# TeensyViewTopTest.net
KiCad netlist of a schematic drawn in EAGLE
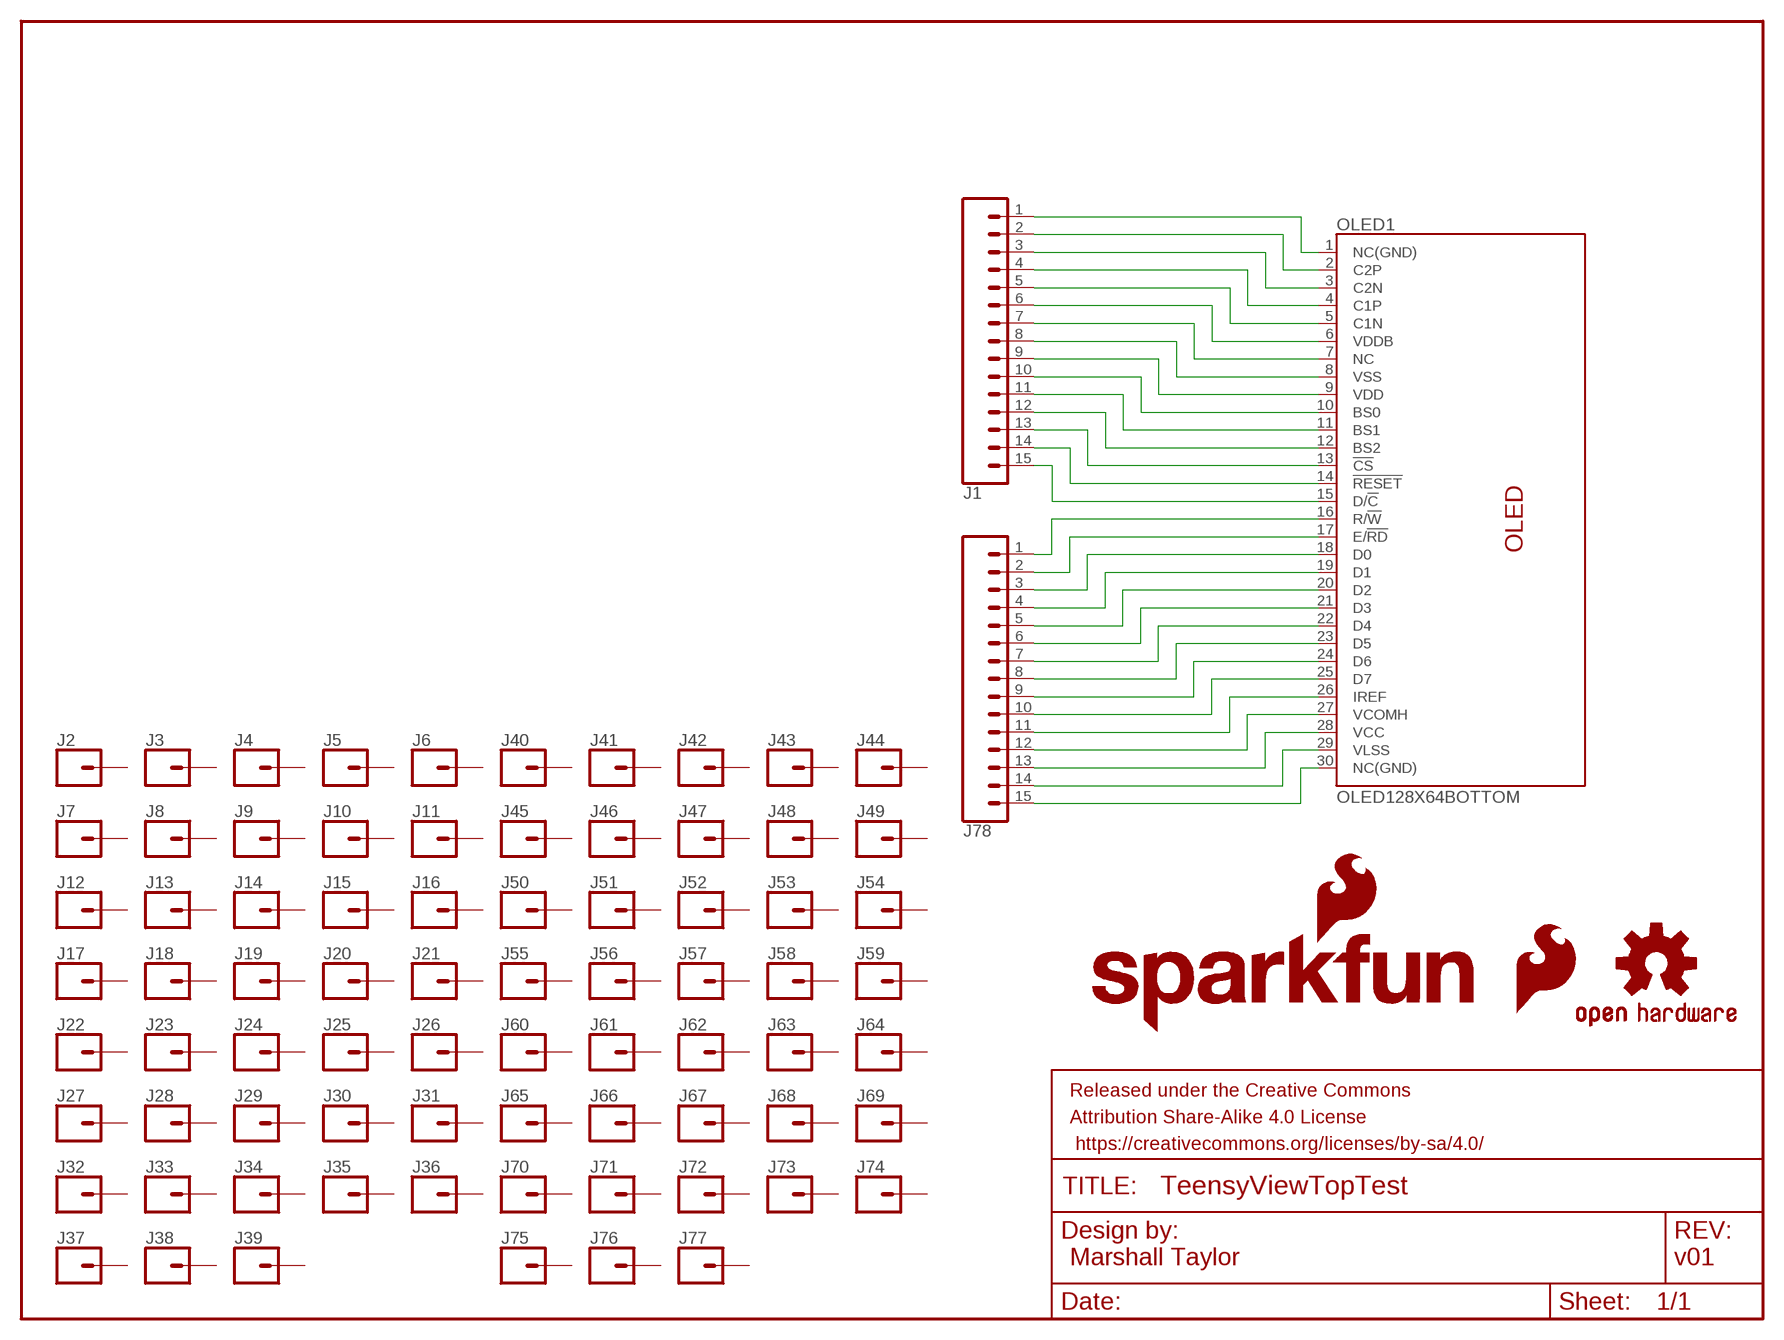
[diagram p0: schematic, sheet 1]

(export (version "E")
  (design (tool "Eeschema 10.0.6"))
  (components
    (comp (ref "FRAME1")
      (value "FRAME-LETTER")
      (footprint "eagle-import:CREATIVE_COMMONS")
      (libsource (lib "eagle-import") (part "FRAME-LETTER"))
    )
    (comp (ref "J1")
      (value "CONN_15")
      (footprint "eagle-import:1X15")
      (libsource (lib "eagle-import") (part "CONN_15"))
    )
    (comp (ref "J2")
      (value "CONN_01PTH_NO_SILK_YES_STOP")
      (footprint "eagle-import:1X01_NO_SILK")
      (libsource (lib "eagle-import") (part "CONN_01PTH_NO_SILK_YES_STOP"))
    )
    (comp (ref "J3")
      (value "CONN_01PTH_NO_SILK_YES_STOP")
      (footprint "eagle-import:1X01_NO_SILK")
      (libsource (lib "eagle-import") (part "CONN_01PTH_NO_SILK_YES_STOP"))
    )
    (comp (ref "J4")
      (value "CONN_01PTH_NO_SILK_YES_STOP")
      (footprint "eagle-import:1X01_NO_SILK")
      (libsource (lib "eagle-import") (part "CONN_01PTH_NO_SILK_YES_STOP"))
    )
    (comp (ref "J5")
      (value "CONN_01PTH_NO_SILK_YES_STOP")
      (footprint "eagle-import:1X01_NO_SILK")
      (libsource (lib "eagle-import") (part "CONN_01PTH_NO_SILK_YES_STOP"))
    )
    (comp (ref "J6")
      (value "CONN_01PTH_NO_SILK_YES_STOP")
      (footprint "eagle-import:1X01_NO_SILK")
      (libsource (lib "eagle-import") (part "CONN_01PTH_NO_SILK_YES_STOP"))
    )
    (comp (ref "J7")
      (value "CONN_01PTH_NO_SILK_YES_STOP")
      (footprint "eagle-import:1X01_NO_SILK")
      (libsource (lib "eagle-import") (part "CONN_01PTH_NO_SILK_YES_STOP"))
    )
    (comp (ref "J8")
      (value "CONN_01PTH_NO_SILK_YES_STOP")
      (footprint "eagle-import:1X01_NO_SILK")
      (libsource (lib "eagle-import") (part "CONN_01PTH_NO_SILK_YES_STOP"))
    )
    (comp (ref "J9")
      (value "CONN_01PTH_NO_SILK_YES_STOP")
      (footprint "eagle-import:1X01_NO_SILK")
      (libsource (lib "eagle-import") (part "CONN_01PTH_NO_SILK_YES_STOP"))
    )
    (comp (ref "J10")
      (value "CONN_01PTH_NO_SILK_YES_STOP")
      (footprint "eagle-import:1X01_NO_SILK")
      (libsource (lib "eagle-import") (part "CONN_01PTH_NO_SILK_YES_STOP"))
    )
    (comp (ref "J11")
      (value "CONN_01PTH_NO_SILK_YES_STOP")
      (footprint "eagle-import:1X01_NO_SILK")
      (libsource (lib "eagle-import") (part "CONN_01PTH_NO_SILK_YES_STOP"))
    )
    (comp (ref "J12")
      (value "CONN_01PTH_NO_SILK_YES_STOP")
      (footprint "eagle-import:1X01_NO_SILK")
      (libsource (lib "eagle-import") (part "CONN_01PTH_NO_SILK_YES_STOP"))
    )
    (comp (ref "J13")
      (value "CONN_01PTH_NO_SILK_YES_STOP")
      (footprint "eagle-import:1X01_NO_SILK")
      (libsource (lib "eagle-import") (part "CONN_01PTH_NO_SILK_YES_STOP"))
    )
    (comp (ref "J14")
      (value "CONN_01PTH_NO_SILK_YES_STOP")
      (footprint "eagle-import:1X01_NO_SILK")
      (libsource (lib "eagle-import") (part "CONN_01PTH_NO_SILK_YES_STOP"))
    )
    (comp (ref "J15")
      (value "CONN_01PTH_NO_SILK_YES_STOP")
      (footprint "eagle-import:1X01_NO_SILK")
      (libsource (lib "eagle-import") (part "CONN_01PTH_NO_SILK_YES_STOP"))
    )
    (comp (ref "J16")
      (value "CONN_01PTH_NO_SILK_YES_STOP")
      (footprint "eagle-import:1X01_NO_SILK")
      (libsource (lib "eagle-import") (part "CONN_01PTH_NO_SILK_YES_STOP"))
    )
    (comp (ref "J17")
      (value "CONN_01PTH_NO_SILK_YES_STOP")
      (footprint "eagle-import:1X01_NO_SILK")
      (libsource (lib "eagle-import") (part "CONN_01PTH_NO_SILK_YES_STOP"))
    )
    (comp (ref "J18")
      (value "CONN_01PTH_NO_SILK_YES_STOP")
      (footprint "eagle-import:1X01_NO_SILK")
      (libsource (lib "eagle-import") (part "CONN_01PTH_NO_SILK_YES_STOP"))
    )
    (comp (ref "J19")
      (value "CONN_01PTH_NO_SILK_YES_STOP")
      (footprint "eagle-import:1X01_NO_SILK")
      (libsource (lib "eagle-import") (part "CONN_01PTH_NO_SILK_YES_STOP"))
    )
    (comp (ref "J20")
      (value "CONN_01PTH_NO_SILK_YES_STOP")
      (footprint "eagle-import:1X01_NO_SILK")
      (libsource (lib "eagle-import") (part "CONN_01PTH_NO_SILK_YES_STOP"))
    )
    (comp (ref "J21")
      (value "CONN_01PTH_NO_SILK_YES_STOP")
      (footprint "eagle-import:1X01_NO_SILK")
      (libsource (lib "eagle-import") (part "CONN_01PTH_NO_SILK_YES_STOP"))
    )
    (comp (ref "J22")
      (value "CONN_01PTH_NO_SILK_YES_STOP")
      (footprint "eagle-import:1X01_NO_SILK")
      (libsource (lib "eagle-import") (part "CONN_01PTH_NO_SILK_YES_STOP"))
    )
    (comp (ref "J23")
      (value "CONN_01PTH_NO_SILK_YES_STOP")
      (footprint "eagle-import:1X01_NO_SILK")
      (libsource (lib "eagle-import") (part "CONN_01PTH_NO_SILK_YES_STOP"))
    )
    (comp (ref "J24")
      (value "CONN_01PTH_NO_SILK_YES_STOP")
      (footprint "eagle-import:1X01_NO_SILK")
      (libsource (lib "eagle-import") (part "CONN_01PTH_NO_SILK_YES_STOP"))
    )
    (comp (ref "J25")
      (value "CONN_01PTH_NO_SILK_YES_STOP")
      (footprint "eagle-import:1X01_NO_SILK")
      (libsource (lib "eagle-import") (part "CONN_01PTH_NO_SILK_YES_STOP"))
    )
    (comp (ref "J26")
      (value "CONN_01PTH_NO_SILK_YES_STOP")
      (footprint "eagle-import:1X01_NO_SILK")
      (libsource (lib "eagle-import") (part "CONN_01PTH_NO_SILK_YES_STOP"))
    )
    (comp (ref "J27")
      (value "CONN_01PTH_NO_SILK_YES_STOP")
      (footprint "eagle-import:1X01_NO_SILK")
      (libsource (lib "eagle-import") (part "CONN_01PTH_NO_SILK_YES_STOP"))
    )
    (comp (ref "J28")
      (value "CONN_01PTH_NO_SILK_YES_STOP")
      (footprint "eagle-import:1X01_NO_SILK")
      (libsource (lib "eagle-import") (part "CONN_01PTH_NO_SILK_YES_STOP"))
    )
    (comp (ref "J29")
      (value "CONN_01PTH_NO_SILK_YES_STOP")
      (footprint "eagle-import:1X01_NO_SILK")
      (libsource (lib "eagle-import") (part "CONN_01PTH_NO_SILK_YES_STOP"))
    )
    (comp (ref "J30")
      (value "CONN_01PTH_NO_SILK_YES_STOP")
      (footprint "eagle-import:1X01_NO_SILK")
      (libsource (lib "eagle-import") (part "CONN_01PTH_NO_SILK_YES_STOP"))
    )
    (comp (ref "J31")
      (value "CONN_01PTH_NO_SILK_YES_STOP")
      (footprint "eagle-import:1X01_NO_SILK")
      (libsource (lib "eagle-import") (part "CONN_01PTH_NO_SILK_YES_STOP"))
    )
    (comp (ref "J32")
      (value "CONN_01PTH_NO_SILK_YES_STOP")
      (footprint "eagle-import:1X01_NO_SILK")
      (libsource (lib "eagle-import") (part "CONN_01PTH_NO_SILK_YES_STOP"))
    )
    (comp (ref "J33")
      (value "CONN_01PTH_NO_SILK_YES_STOP")
      (footprint "eagle-import:1X01_NO_SILK")
      (libsource (lib "eagle-import") (part "CONN_01PTH_NO_SILK_YES_STOP"))
    )
    (comp (ref "J34")
      (value "CONN_01PTH_NO_SILK_YES_STOP")
      (footprint "eagle-import:1X01_NO_SILK")
      (libsource (lib "eagle-import") (part "CONN_01PTH_NO_SILK_YES_STOP"))
    )
    (comp (ref "J35")
      (value "CONN_01PTH_NO_SILK_YES_STOP")
      (footprint "eagle-import:1X01_NO_SILK")
      (libsource (lib "eagle-import") (part "CONN_01PTH_NO_SILK_YES_STOP"))
    )
    (comp (ref "J36")
      (value "CONN_01PTH_NO_SILK_YES_STOP")
      (footprint "eagle-import:1X01_NO_SILK")
      (libsource (lib "eagle-import") (part "CONN_01PTH_NO_SILK_YES_STOP"))
    )
    (comp (ref "J37")
      (value "CONN_01PTH_NO_SILK_YES_STOP")
      (footprint "eagle-import:1X01_NO_SILK")
      (libsource (lib "eagle-import") (part "CONN_01PTH_NO_SILK_YES_STOP"))
    )
    (comp (ref "J38")
      (value "CONN_01PTH_NO_SILK_YES_STOP")
      (footprint "eagle-import:1X01_NO_SILK")
      (libsource (lib "eagle-import") (part "CONN_01PTH_NO_SILK_YES_STOP"))
    )
    (comp (ref "J39")
      (value "CONN_01PTH_NO_SILK_YES_STOP")
      (footprint "eagle-import:1X01_NO_SILK")
      (libsource (lib "eagle-import") (part "CONN_01PTH_NO_SILK_YES_STOP"))
    )
    (comp (ref "J40")
      (value "CONN_01PTH_NO_SILK_YES_STOP")
      (footprint "eagle-import:1X01_NO_SILK")
      (libsource (lib "eagle-import") (part "CONN_01PTH_NO_SILK_YES_STOP"))
    )
    (comp (ref "J41")
      (value "CONN_01PTH_NO_SILK_YES_STOP")
      (footprint "eagle-import:1X01_NO_SILK")
      (libsource (lib "eagle-import") (part "CONN_01PTH_NO_SILK_YES_STOP"))
    )
    (comp (ref "J42")
      (value "CONN_01PTH_NO_SILK_YES_STOP")
      (footprint "eagle-import:1X01_NO_SILK")
      (libsource (lib "eagle-import") (part "CONN_01PTH_NO_SILK_YES_STOP"))
    )
    (comp (ref "J43")
      (value "CONN_01PTH_NO_SILK_YES_STOP")
      (footprint "eagle-import:1X01_NO_SILK")
      (libsource (lib "eagle-import") (part "CONN_01PTH_NO_SILK_YES_STOP"))
    )
    (comp (ref "J44")
      (value "CONN_01PTH_NO_SILK_YES_STOP")
      (footprint "eagle-import:1X01_NO_SILK")
      (libsource (lib "eagle-import") (part "CONN_01PTH_NO_SILK_YES_STOP"))
    )
    (comp (ref "J45")
      (value "CONN_01PTH_NO_SILK_YES_STOP")
      (footprint "eagle-import:1X01_NO_SILK")
      (libsource (lib "eagle-import") (part "CONN_01PTH_NO_SILK_YES_STOP"))
    )
    (comp (ref "J46")
      (value "CONN_01PTH_NO_SILK_YES_STOP")
      (footprint "eagle-import:1X01_NO_SILK")
      (libsource (lib "eagle-import") (part "CONN_01PTH_NO_SILK_YES_STOP"))
    )
    (comp (ref "J47")
      (value "CONN_01PTH_NO_SILK_YES_STOP")
      (footprint "eagle-import:1X01_NO_SILK")
      (libsource (lib "eagle-import") (part "CONN_01PTH_NO_SILK_YES_STOP"))
    )
    (comp (ref "J48")
      (value "CONN_01PTH_NO_SILK_YES_STOP")
      (footprint "eagle-import:1X01_NO_SILK")
      (libsource (lib "eagle-import") (part "CONN_01PTH_NO_SILK_YES_STOP"))
    )
    (comp (ref "J49")
      (value "CONN_01PTH_NO_SILK_YES_STOP")
      (footprint "eagle-import:1X01_NO_SILK")
      (libsource (lib "eagle-import") (part "CONN_01PTH_NO_SILK_YES_STOP"))
    )
    (comp (ref "J50")
      (value "CONN_01PTH_NO_SILK_YES_STOP")
      (footprint "eagle-import:1X01_NO_SILK")
      (libsource (lib "eagle-import") (part "CONN_01PTH_NO_SILK_YES_STOP"))
    )
    (comp (ref "J51")
      (value "CONN_01PTH_NO_SILK_YES_STOP")
      (footprint "eagle-import:1X01_NO_SILK")
      (libsource (lib "eagle-import") (part "CONN_01PTH_NO_SILK_YES_STOP"))
    )
    (comp (ref "J52")
      (value "CONN_01PTH_NO_SILK_YES_STOP")
      (footprint "eagle-import:1X01_NO_SILK")
      (libsource (lib "eagle-import") (part "CONN_01PTH_NO_SILK_YES_STOP"))
    )
    (comp (ref "J53")
      (value "CONN_01PTH_NO_SILK_YES_STOP")
      (footprint "eagle-import:1X01_NO_SILK")
      (libsource (lib "eagle-import") (part "CONN_01PTH_NO_SILK_YES_STOP"))
    )
    (comp (ref "J54")
      (value "CONN_01PTH_NO_SILK_YES_STOP")
      (footprint "eagle-import:1X01_NO_SILK")
      (libsource (lib "eagle-import") (part "CONN_01PTH_NO_SILK_YES_STOP"))
    )
    (comp (ref "J55")
      (value "CONN_01PTH_NO_SILK_YES_STOP")
      (footprint "eagle-import:1X01_NO_SILK")
      (libsource (lib "eagle-import") (part "CONN_01PTH_NO_SILK_YES_STOP"))
    )
    (comp (ref "J56")
      (value "CONN_01PTH_NO_SILK_YES_STOP")
      (footprint "eagle-import:1X01_NO_SILK")
      (libsource (lib "eagle-import") (part "CONN_01PTH_NO_SILK_YES_STOP"))
    )
    (comp (ref "J57")
      (value "CONN_01PTH_NO_SILK_YES_STOP")
      (footprint "eagle-import:1X01_NO_SILK")
      (libsource (lib "eagle-import") (part "CONN_01PTH_NO_SILK_YES_STOP"))
    )
    (comp (ref "J58")
      (value "CONN_01PTH_NO_SILK_YES_STOP")
      (footprint "eagle-import:1X01_NO_SILK")
      (libsource (lib "eagle-import") (part "CONN_01PTH_NO_SILK_YES_STOP"))
    )
    (comp (ref "J59")
      (value "CONN_01PTH_NO_SILK_YES_STOP")
      (footprint "eagle-import:1X01_NO_SILK")
      (libsource (lib "eagle-import") (part "CONN_01PTH_NO_SILK_YES_STOP"))
    )
    (comp (ref "J60")
      (value "CONN_01PTH_NO_SILK_YES_STOP")
      (footprint "eagle-import:1X01_NO_SILK")
      (libsource (lib "eagle-import") (part "CONN_01PTH_NO_SILK_YES_STOP"))
    )
    (comp (ref "J61")
      (value "CONN_01PTH_NO_SILK_YES_STOP")
      (footprint "eagle-import:1X01_NO_SILK")
      (libsource (lib "eagle-import") (part "CONN_01PTH_NO_SILK_YES_STOP"))
    )
    (comp (ref "J62")
      (value "CONN_01PTH_NO_SILK_YES_STOP")
      (footprint "eagle-import:1X01_NO_SILK")
      (libsource (lib "eagle-import") (part "CONN_01PTH_NO_SILK_YES_STOP"))
    )
    (comp (ref "J63")
      (value "CONN_01PTH_NO_SILK_YES_STOP")
      (footprint "eagle-import:1X01_NO_SILK")
      (libsource (lib "eagle-import") (part "CONN_01PTH_NO_SILK_YES_STOP"))
    )
    (comp (ref "J64")
      (value "CONN_01PTH_NO_SILK_YES_STOP")
      (footprint "eagle-import:1X01_NO_SILK")
      (libsource (lib "eagle-import") (part "CONN_01PTH_NO_SILK_YES_STOP"))
    )
    (comp (ref "J65")
      (value "CONN_01PTH_NO_SILK_YES_STOP")
      (footprint "eagle-import:1X01_NO_SILK")
      (libsource (lib "eagle-import") (part "CONN_01PTH_NO_SILK_YES_STOP"))
    )
    (comp (ref "J66")
      (value "CONN_01PTH_NO_SILK_YES_STOP")
      (footprint "eagle-import:1X01_NO_SILK")
      (libsource (lib "eagle-import") (part "CONN_01PTH_NO_SILK_YES_STOP"))
    )
    (comp (ref "J67")
      (value "CONN_01PTH_NO_SILK_YES_STOP")
      (footprint "eagle-import:1X01_NO_SILK")
      (libsource (lib "eagle-import") (part "CONN_01PTH_NO_SILK_YES_STOP"))
    )
    (comp (ref "J68")
      (value "CONN_01PTH_NO_SILK_YES_STOP")
      (footprint "eagle-import:1X01_NO_SILK")
      (libsource (lib "eagle-import") (part "CONN_01PTH_NO_SILK_YES_STOP"))
    )
    (comp (ref "J69")
      (value "CONN_01PTH_NO_SILK_YES_STOP")
      (footprint "eagle-import:1X01_NO_SILK")
      (libsource (lib "eagle-import") (part "CONN_01PTH_NO_SILK_YES_STOP"))
    )
    (comp (ref "J70")
      (value "CONN_01PTH_NO_SILK_YES_STOP")
      (footprint "eagle-import:1X01_NO_SILK")
      (libsource (lib "eagle-import") (part "CONN_01PTH_NO_SILK_YES_STOP"))
    )
    (comp (ref "J71")
      (value "CONN_01PTH_NO_SILK_YES_STOP")
      (footprint "eagle-import:1X01_NO_SILK")
      (libsource (lib "eagle-import") (part "CONN_01PTH_NO_SILK_YES_STOP"))
    )
    (comp (ref "J72")
      (value "CONN_01PTH_NO_SILK_YES_STOP")
      (footprint "eagle-import:1X01_NO_SILK")
      (libsource (lib "eagle-import") (part "CONN_01PTH_NO_SILK_YES_STOP"))
    )
    (comp (ref "J73")
      (value "CONN_01PTH_NO_SILK_YES_STOP")
      (footprint "eagle-import:1X01_NO_SILK")
      (libsource (lib "eagle-import") (part "CONN_01PTH_NO_SILK_YES_STOP"))
    )
    (comp (ref "J74")
      (value "CONN_01PTH_NO_SILK_YES_STOP")
      (footprint "eagle-import:1X01_NO_SILK")
      (libsource (lib "eagle-import") (part "CONN_01PTH_NO_SILK_YES_STOP"))
    )
    (comp (ref "J75")
      (value "CONN_01PTH_NO_SILK_YES_STOP")
      (footprint "eagle-import:1X01_NO_SILK")
      (libsource (lib "eagle-import") (part "CONN_01PTH_NO_SILK_YES_STOP"))
    )
    (comp (ref "J76")
      (value "CONN_01PTH_NO_SILK_YES_STOP")
      (footprint "eagle-import:1X01_NO_SILK")
      (libsource (lib "eagle-import") (part "CONN_01PTH_NO_SILK_YES_STOP"))
    )
    (comp (ref "J77")
      (value "CONN_01PTH_NO_SILK_YES_STOP")
      (footprint "eagle-import:1X01_NO_SILK")
      (libsource (lib "eagle-import") (part "CONN_01PTH_NO_SILK_YES_STOP"))
    )
    (comp (ref "J78")
      (value "CONN_15")
      (footprint "eagle-import:1X15")
      (libsource (lib "eagle-import") (part "CONN_15"))
    )
    (comp (ref "LOGO1")
      (value "SFE_LOGO_FLAME.1_INCH")
      (footprint "eagle-import:SFE_LOGO_FLAME_.1")
      (libsource (lib "eagle-import") (part "SFE_LOGO_FLAME.1_INCH"))
    )
    (comp (ref "LOGO2")
      (value "OSHW-LOGOS")
      (footprint "eagle-import:OSHW-LOGO-S")
      (libsource (lib "eagle-import") (part "OSHW-LOGOS"))
    )
    (comp (ref "LOGO3")
      (value "SFE_LOGO_NAME_FLAME.1_INCH")
      (footprint "eagle-import:SFE_LOGO_NAME_FLAME_.1")
      (libsource (lib "eagle-import") (part "SFE_LOGO_NAME_FLAME.1_INCH"))
    )
    (comp (ref "OLED1")
      (value "OLED128X64BOTTOM")
      (footprint "eagle-import:OLED-UG-2832HLBEG04")
      (libsource (lib "eagle-import") (part "OLED128X64BOTTOM"))
    )
  )
  (nets
    (net (code "1") (name "Net-(J1-Pad1)") (class "Default")
      (node (ref "J1") (pin "1") (pinfunction "1_1") (pintype "passive"))
      (node (ref "OLED1") (pin "1") (pinfunction "NC(GND)_1") (pintype "bidirectional"))
    )
    (net (code "2") (name "Net-(J78-Pad15)") (class "Default")
      (node (ref "J78") (pin "15") (pinfunction "15_15") (pintype "passive"))
      (node (ref "OLED1") (pin "30") (pinfunction "NC(GND)_30") (pintype "bidirectional"))
    )
    (net (code "3") (name "Net-(OLED1-BS0)") (class "Default")
      (node (ref "J1") (pin "10") (pinfunction "10_10") (pintype "passive"))
      (node (ref "OLED1") (pin "10") (pinfunction "BS0_10") (pintype "bidirectional"))
    )
    (net (code "4") (name "Net-(OLED1-BS1)") (class "Default")
      (node (ref "J1") (pin "11") (pinfunction "11_11") (pintype "passive"))
      (node (ref "OLED1") (pin "11") (pinfunction "BS1_11") (pintype "bidirectional"))
    )
    (net (code "5") (name "Net-(OLED1-BS2)") (class "Default")
      (node (ref "J1") (pin "12") (pinfunction "12_12") (pintype "passive"))
      (node (ref "OLED1") (pin "12") (pinfunction "BS2_12") (pintype "bidirectional"))
    )
    (net (code "6") (name "Net-(OLED1-C1N)") (class "Default")
      (node (ref "J1") (pin "5") (pinfunction "5_5") (pintype "passive"))
      (node (ref "OLED1") (pin "5") (pinfunction "C1N_5") (pintype "bidirectional"))
    )
    (net (code "7") (name "Net-(OLED1-C1P)") (class "Default")
      (node (ref "J1") (pin "4") (pinfunction "4_4") (pintype "passive"))
      (node (ref "OLED1") (pin "4") (pinfunction "C1P_4") (pintype "bidirectional"))
    )
    (net (code "8") (name "Net-(OLED1-C2N)") (class "Default")
      (node (ref "J1") (pin "3") (pinfunction "3_3") (pintype "passive"))
      (node (ref "OLED1") (pin "3") (pinfunction "C2N_3") (pintype "bidirectional"))
    )
    (net (code "9") (name "Net-(OLED1-C2P)") (class "Default")
      (node (ref "J1") (pin "2") (pinfunction "2_2") (pintype "passive"))
      (node (ref "OLED1") (pin "2") (pinfunction "C2P_2") (pintype "bidirectional"))
    )
    (net (code "10") (name "Net-(OLED1-D0)") (class "Default")
      (node (ref "J78") (pin "3") (pinfunction "3_3") (pintype "passive"))
      (node (ref "OLED1") (pin "18") (pinfunction "D0_18") (pintype "bidirectional"))
    )
    (net (code "11") (name "Net-(OLED1-D1)") (class "Default")
      (node (ref "J78") (pin "4") (pinfunction "4_4") (pintype "passive"))
      (node (ref "OLED1") (pin "19") (pinfunction "D1_19") (pintype "bidirectional"))
    )
    (net (code "12") (name "Net-(OLED1-D2)") (class "Default")
      (node (ref "J78") (pin "5") (pinfunction "5_5") (pintype "passive"))
      (node (ref "OLED1") (pin "20") (pinfunction "D2_20") (pintype "bidirectional"))
    )
    (net (code "13") (name "Net-(OLED1-D3)") (class "Default")
      (node (ref "J78") (pin "6") (pinfunction "6_6") (pintype "passive"))
      (node (ref "OLED1") (pin "21") (pinfunction "D3_21") (pintype "bidirectional"))
    )
    (net (code "14") (name "Net-(OLED1-D4)") (class "Default")
      (node (ref "J78") (pin "7") (pinfunction "7_7") (pintype "passive"))
      (node (ref "OLED1") (pin "22") (pinfunction "D4_22") (pintype "bidirectional"))
    )
    (net (code "15") (name "Net-(OLED1-D5)") (class "Default")
      (node (ref "J78") (pin "8") (pinfunction "8_8") (pintype "passive"))
      (node (ref "OLED1") (pin "23") (pinfunction "D5_23") (pintype "bidirectional"))
    )
    (net (code "16") (name "Net-(OLED1-D6)") (class "Default")
      (node (ref "J78") (pin "9") (pinfunction "9_9") (pintype "passive"))
      (node (ref "OLED1") (pin "24") (pinfunction "D6_24") (pintype "bidirectional"))
    )
    (net (code "17") (name "Net-(OLED1-D7)") (class "Default")
      (node (ref "J78") (pin "10") (pinfunction "10_10") (pintype "passive"))
      (node (ref "OLED1") (pin "25") (pinfunction "D7_25") (pintype "bidirectional"))
    )
    (net (code "18") (name "Net-(OLED1-D{slash}~{C})") (class "Default")
      (node (ref "J1") (pin "15") (pinfunction "15_15") (pintype "passive"))
      (node (ref "OLED1") (pin "15") (pinfunction "D/~{C}_15") (pintype "bidirectional"))
    )
    (net (code "19") (name "Net-(OLED1-E{slash}~{RD})") (class "Default")
      (node (ref "J78") (pin "2") (pinfunction "2_2") (pintype "passive"))
      (node (ref "OLED1") (pin "17") (pinfunction "E/~{RD}_17") (pintype "bidirectional"))
    )
    (net (code "20") (name "Net-(OLED1-IREF)") (class "Default")
      (node (ref "J78") (pin "11") (pinfunction "11_11") (pintype "passive"))
      (node (ref "OLED1") (pin "26") (pinfunction "IREF_26") (pintype "bidirectional"))
    )
    (net (code "21") (name "Net-(OLED1-NC)") (class "Default")
      (node (ref "J1") (pin "7") (pinfunction "7_7") (pintype "passive"))
      (node (ref "OLED1") (pin "7") (pinfunction "NC_7") (pintype "bidirectional"))
    )
    (net (code "22") (name "Net-(OLED1-R{slash}~{W})") (class "Default")
      (node (ref "J78") (pin "1") (pinfunction "1_1") (pintype "passive"))
      (node (ref "OLED1") (pin "16") (pinfunction "R/~{W}_16") (pintype "bidirectional"))
    )
    (net (code "23") (name "Net-(OLED1-VCC)") (class "Default")
      (node (ref "J78") (pin "13") (pinfunction "13_13") (pintype "passive"))
      (node (ref "OLED1") (pin "28") (pinfunction "VCC_28") (pintype "bidirectional"))
    )
    (net (code "24") (name "Net-(OLED1-VCOMH)") (class "Default")
      (node (ref "J78") (pin "12") (pinfunction "12_12") (pintype "passive"))
      (node (ref "OLED1") (pin "27") (pinfunction "VCOMH_27") (pintype "bidirectional"))
    )
    (net (code "25") (name "Net-(OLED1-VDD)") (class "Default")
      (node (ref "J1") (pin "9") (pinfunction "9_9") (pintype "passive"))
      (node (ref "OLED1") (pin "9") (pinfunction "VDD_9") (pintype "bidirectional"))
    )
    (net (code "26") (name "Net-(OLED1-VDDB)") (class "Default")
      (node (ref "J1") (pin "6") (pinfunction "6_6") (pintype "passive"))
      (node (ref "OLED1") (pin "6") (pinfunction "VDDB_6") (pintype "bidirectional"))
    )
    (net (code "27") (name "Net-(OLED1-VLSS)") (class "Default")
      (node (ref "J78") (pin "14") (pinfunction "14_14") (pintype "passive"))
      (node (ref "OLED1") (pin "29") (pinfunction "VLSS_29") (pintype "bidirectional"))
    )
    (net (code "28") (name "Net-(OLED1-VSS)") (class "Default")
      (node (ref "J1") (pin "8") (pinfunction "8_8") (pintype "passive"))
      (node (ref "OLED1") (pin "8") (pinfunction "VSS_8") (pintype "bidirectional"))
    )
    (net (code "29") (name "Net-(OLED1-~{CS})") (class "Default")
      (node (ref "J1") (pin "13") (pinfunction "13_13") (pintype "passive"))
      (node (ref "OLED1") (pin "13") (pinfunction "~{CS}_13") (pintype "bidirectional"))
    )
    (net (code "30") (name "Net-(OLED1-~{RESET})") (class "Default")
      (node (ref "J1") (pin "14") (pinfunction "14_14") (pintype "passive"))
      (node (ref "OLED1") (pin "14") (pinfunction "~{RESET}_14") (pintype "bidirectional"))
    )
    (net (code "31") (name "unconnected-(J2-Pad1)") (class "Default")
      (node (ref "J2") (pin "1") (pinfunction "1_1") (pintype "passive"))
    )
    (net (code "32") (name "unconnected-(J3-Pad1)") (class "Default")
      (node (ref "J3") (pin "1") (pinfunction "1_1") (pintype "passive"))
    )
    (net (code "33") (name "unconnected-(J4-Pad1)") (class "Default")
      (node (ref "J4") (pin "1") (pinfunction "1_1") (pintype "passive"))
    )
    (net (code "34") (name "unconnected-(J5-Pad1)") (class "Default")
      (node (ref "J5") (pin "1") (pinfunction "1_1") (pintype "passive"))
    )
    (net (code "35") (name "unconnected-(J6-Pad1)") (class "Default")
      (node (ref "J6") (pin "1") (pinfunction "1_1") (pintype "passive"))
    )
    (net (code "36") (name "unconnected-(J7-Pad1)") (class "Default")
      (node (ref "J7") (pin "1") (pinfunction "1_1") (pintype "passive"))
    )
    (net (code "37") (name "unconnected-(J8-Pad1)") (class "Default")
      (node (ref "J8") (pin "1") (pinfunction "1_1") (pintype "passive"))
    )
    (net (code "38") (name "unconnected-(J9-Pad1)") (class "Default")
      (node (ref "J9") (pin "1") (pinfunction "1_1") (pintype "passive"))
    )
    (net (code "39") (name "unconnected-(J10-Pad1)") (class "Default")
      (node (ref "J10") (pin "1") (pinfunction "1_1") (pintype "passive"))
    )
    (net (code "40") (name "unconnected-(J11-Pad1)") (class "Default")
      (node (ref "J11") (pin "1") (pinfunction "1_1") (pintype "passive"))
    )
    (net (code "41") (name "unconnected-(J12-Pad1)") (class "Default")
      (node (ref "J12") (pin "1") (pinfunction "1_1") (pintype "passive"))
    )
    (net (code "42") (name "unconnected-(J13-Pad1)") (class "Default")
      (node (ref "J13") (pin "1") (pinfunction "1_1") (pintype "passive"))
    )
    (net (code "43") (name "unconnected-(J14-Pad1)") (class "Default")
      (node (ref "J14") (pin "1") (pinfunction "1_1") (pintype "passive"))
    )
    (net (code "44") (name "unconnected-(J15-Pad1)") (class "Default")
      (node (ref "J15") (pin "1") (pinfunction "1_1") (pintype "passive"))
    )
    (net (code "45") (name "unconnected-(J16-Pad1)") (class "Default")
      (node (ref "J16") (pin "1") (pinfunction "1_1") (pintype "passive"))
    )
    (net (code "46") (name "unconnected-(J17-Pad1)") (class "Default")
      (node (ref "J17") (pin "1") (pinfunction "1_1") (pintype "passive"))
    )
    (net (code "47") (name "unconnected-(J18-Pad1)") (class "Default")
      (node (ref "J18") (pin "1") (pinfunction "1_1") (pintype "passive"))
    )
    (net (code "48") (name "unconnected-(J19-Pad1)") (class "Default")
      (node (ref "J19") (pin "1") (pinfunction "1_1") (pintype "passive"))
    )
    (net (code "49") (name "unconnected-(J20-Pad1)") (class "Default")
      (node (ref "J20") (pin "1") (pinfunction "1_1") (pintype "passive"))
    )
    (net (code "50") (name "unconnected-(J21-Pad1)") (class "Default")
      (node (ref "J21") (pin "1") (pinfunction "1_1") (pintype "passive"))
    )
    (net (code "51") (name "unconnected-(J22-Pad1)") (class "Default")
      (node (ref "J22") (pin "1") (pinfunction "1_1") (pintype "passive"))
    )
    (net (code "52") (name "unconnected-(J23-Pad1)") (class "Default")
      (node (ref "J23") (pin "1") (pinfunction "1_1") (pintype "passive"))
    )
    (net (code "53") (name "unconnected-(J24-Pad1)") (class "Default")
      (node (ref "J24") (pin "1") (pinfunction "1_1") (pintype "passive"))
    )
    (net (code "54") (name "unconnected-(J25-Pad1)") (class "Default")
      (node (ref "J25") (pin "1") (pinfunction "1_1") (pintype "passive"))
    )
    (net (code "55") (name "unconnected-(J26-Pad1)") (class "Default")
      (node (ref "J26") (pin "1") (pinfunction "1_1") (pintype "passive"))
    )
    (net (code "56") (name "unconnected-(J27-Pad1)") (class "Default")
      (node (ref "J27") (pin "1") (pinfunction "1_1") (pintype "passive"))
    )
    (net (code "57") (name "unconnected-(J28-Pad1)") (class "Default")
      (node (ref "J28") (pin "1") (pinfunction "1_1") (pintype "passive"))
    )
    (net (code "58") (name "unconnected-(J29-Pad1)") (class "Default")
      (node (ref "J29") (pin "1") (pinfunction "1_1") (pintype "passive"))
    )
    (net (code "59") (name "unconnected-(J30-Pad1)") (class "Default")
      (node (ref "J30") (pin "1") (pinfunction "1_1") (pintype "passive"))
    )
    (net (code "60") (name "unconnected-(J31-Pad1)") (class "Default")
      (node (ref "J31") (pin "1") (pinfunction "1_1") (pintype "passive"))
    )
    (net (code "61") (name "unconnected-(J32-Pad1)") (class "Default")
      (node (ref "J32") (pin "1") (pinfunction "1_1") (pintype "passive"))
    )
    (net (code "62") (name "unconnected-(J33-Pad1)") (class "Default")
      (node (ref "J33") (pin "1") (pinfunction "1_1") (pintype "passive"))
    )
    (net (code "63") (name "unconnected-(J34-Pad1)") (class "Default")
      (node (ref "J34") (pin "1") (pinfunction "1_1") (pintype "passive"))
    )
    (net (code "64") (name "unconnected-(J35-Pad1)") (class "Default")
      (node (ref "J35") (pin "1") (pinfunction "1_1") (pintype "passive"))
    )
    (net (code "65") (name "unconnected-(J36-Pad1)") (class "Default")
      (node (ref "J36") (pin "1") (pinfunction "1_1") (pintype "passive"))
    )
    (net (code "66") (name "unconnected-(J37-Pad1)") (class "Default")
      (node (ref "J37") (pin "1") (pinfunction "1_1") (pintype "passive"))
    )
    (net (code "67") (name "unconnected-(J38-Pad1)") (class "Default")
      (node (ref "J38") (pin "1") (pinfunction "1_1") (pintype "passive"))
    )
    (net (code "68") (name "unconnected-(J39-Pad1)") (class "Default")
      (node (ref "J39") (pin "1") (pinfunction "1_1") (pintype "passive"))
    )
    (net (code "69") (name "unconnected-(J40-Pad1)") (class "Default")
      (node (ref "J40") (pin "1") (pinfunction "1_1") (pintype "passive"))
    )
    (net (code "70") (name "unconnected-(J41-Pad1)") (class "Default")
      (node (ref "J41") (pin "1") (pinfunction "1_1") (pintype "passive"))
    )
    (net (code "71") (name "unconnected-(J42-Pad1)") (class "Default")
      (node (ref "J42") (pin "1") (pinfunction "1_1") (pintype "passive"))
    )
    (net (code "72") (name "unconnected-(J43-Pad1)") (class "Default")
      (node (ref "J43") (pin "1") (pinfunction "1_1") (pintype "passive"))
    )
    (net (code "73") (name "unconnected-(J44-Pad1)") (class "Default")
      (node (ref "J44") (pin "1") (pinfunction "1_1") (pintype "passive"))
    )
    (net (code "74") (name "unconnected-(J45-Pad1)") (class "Default")
      (node (ref "J45") (pin "1") (pinfunction "1_1") (pintype "passive"))
    )
    (net (code "75") (name "unconnected-(J46-Pad1)") (class "Default")
      (node (ref "J46") (pin "1") (pinfunction "1_1") (pintype "passive"))
    )
    (net (code "76") (name "unconnected-(J47-Pad1)") (class "Default")
      (node (ref "J47") (pin "1") (pinfunction "1_1") (pintype "passive"))
    )
    (net (code "77") (name "unconnected-(J48-Pad1)") (class "Default")
      (node (ref "J48") (pin "1") (pinfunction "1_1") (pintype "passive"))
    )
    (net (code "78") (name "unconnected-(J49-Pad1)") (class "Default")
      (node (ref "J49") (pin "1") (pinfunction "1_1") (pintype "passive"))
    )
    (net (code "79") (name "unconnected-(J50-Pad1)") (class "Default")
      (node (ref "J50") (pin "1") (pinfunction "1_1") (pintype "passive"))
    )
    (net (code "80") (name "unconnected-(J51-Pad1)") (class "Default")
      (node (ref "J51") (pin "1") (pinfunction "1_1") (pintype "passive"))
    )
    (net (code "81") (name "unconnected-(J52-Pad1)") (class "Default")
      (node (ref "J52") (pin "1") (pinfunction "1_1") (pintype "passive"))
    )
    (net (code "82") (name "unconnected-(J53-Pad1)") (class "Default")
      (node (ref "J53") (pin "1") (pinfunction "1_1") (pintype "passive"))
    )
    (net (code "83") (name "unconnected-(J54-Pad1)") (class "Default")
      (node (ref "J54") (pin "1") (pinfunction "1_1") (pintype "passive"))
    )
    (net (code "84") (name "unconnected-(J55-Pad1)") (class "Default")
      (node (ref "J55") (pin "1") (pinfunction "1_1") (pintype "passive"))
    )
    (net (code "85") (name "unconnected-(J56-Pad1)") (class "Default")
      (node (ref "J56") (pin "1") (pinfunction "1_1") (pintype "passive"))
    )
    (net (code "86") (name "unconnected-(J57-Pad1)") (class "Default")
      (node (ref "J57") (pin "1") (pinfunction "1_1") (pintype "passive"))
    )
    (net (code "87") (name "unconnected-(J58-Pad1)") (class "Default")
      (node (ref "J58") (pin "1") (pinfunction "1_1") (pintype "passive"))
    )
    (net (code "88") (name "unconnected-(J59-Pad1)") (class "Default")
      (node (ref "J59") (pin "1") (pinfunction "1_1") (pintype "passive"))
    )
    (net (code "89") (name "unconnected-(J60-Pad1)") (class "Default")
      (node (ref "J60") (pin "1") (pinfunction "1_1") (pintype "passive"))
    )
    (net (code "90") (name "unconnected-(J61-Pad1)") (class "Default")
      (node (ref "J61") (pin "1") (pinfunction "1_1") (pintype "passive"))
    )
    (net (code "91") (name "unconnected-(J62-Pad1)") (class "Default")
      (node (ref "J62") (pin "1") (pinfunction "1_1") (pintype "passive"))
    )
    (net (code "92") (name "unconnected-(J63-Pad1)") (class "Default")
      (node (ref "J63") (pin "1") (pinfunction "1_1") (pintype "passive"))
    )
    (net (code "93") (name "unconnected-(J64-Pad1)") (class "Default")
      (node (ref "J64") (pin "1") (pinfunction "1_1") (pintype "passive"))
    )
    (net (code "94") (name "unconnected-(J65-Pad1)") (class "Default")
      (node (ref "J65") (pin "1") (pinfunction "1_1") (pintype "passive"))
    )
    (net (code "95") (name "unconnected-(J66-Pad1)") (class "Default")
      (node (ref "J66") (pin "1") (pinfunction "1_1") (pintype "passive"))
    )
    (net (code "96") (name "unconnected-(J67-Pad1)") (class "Default")
      (node (ref "J67") (pin "1") (pinfunction "1_1") (pintype "passive"))
    )
    (net (code "97") (name "unconnected-(J68-Pad1)") (class "Default")
      (node (ref "J68") (pin "1") (pinfunction "1_1") (pintype "passive"))
    )
    (net (code "98") (name "unconnected-(J69-Pad1)") (class "Default")
      (node (ref "J69") (pin "1") (pinfunction "1_1") (pintype "passive"))
    )
    (net (code "99") (name "unconnected-(J70-Pad1)") (class "Default")
      (node (ref "J70") (pin "1") (pinfunction "1_1") (pintype "passive"))
    )
    (net (code "100") (name "unconnected-(J71-Pad1)") (class "Default")
      (node (ref "J71") (pin "1") (pinfunction "1_1") (pintype "passive"))
    )
    (net (code "101") (name "unconnected-(J72-Pad1)") (class "Default")
      (node (ref "J72") (pin "1") (pinfunction "1_1") (pintype "passive"))
    )
    (net (code "102") (name "unconnected-(J73-Pad1)") (class "Default")
      (node (ref "J73") (pin "1") (pinfunction "1_1") (pintype "passive"))
    )
    (net (code "103") (name "unconnected-(J74-Pad1)") (class "Default")
      (node (ref "J74") (pin "1") (pinfunction "1_1") (pintype "passive"))
    )
    (net (code "104") (name "unconnected-(J75-Pad1)") (class "Default")
      (node (ref "J75") (pin "1") (pinfunction "1_1") (pintype "passive"))
    )
    (net (code "105") (name "unconnected-(J76-Pad1)") (class "Default")
      (node (ref "J76") (pin "1") (pinfunction "1_1") (pintype "passive"))
    )
    (net (code "106") (name "unconnected-(J77-Pad1)") (class "Default")
      (node (ref "J77") (pin "1") (pinfunction "1_1") (pintype "passive"))
    )
  )
)
